# SX1278_STM32.net
KiCad netlist of a schematic drawn in Altium Designer
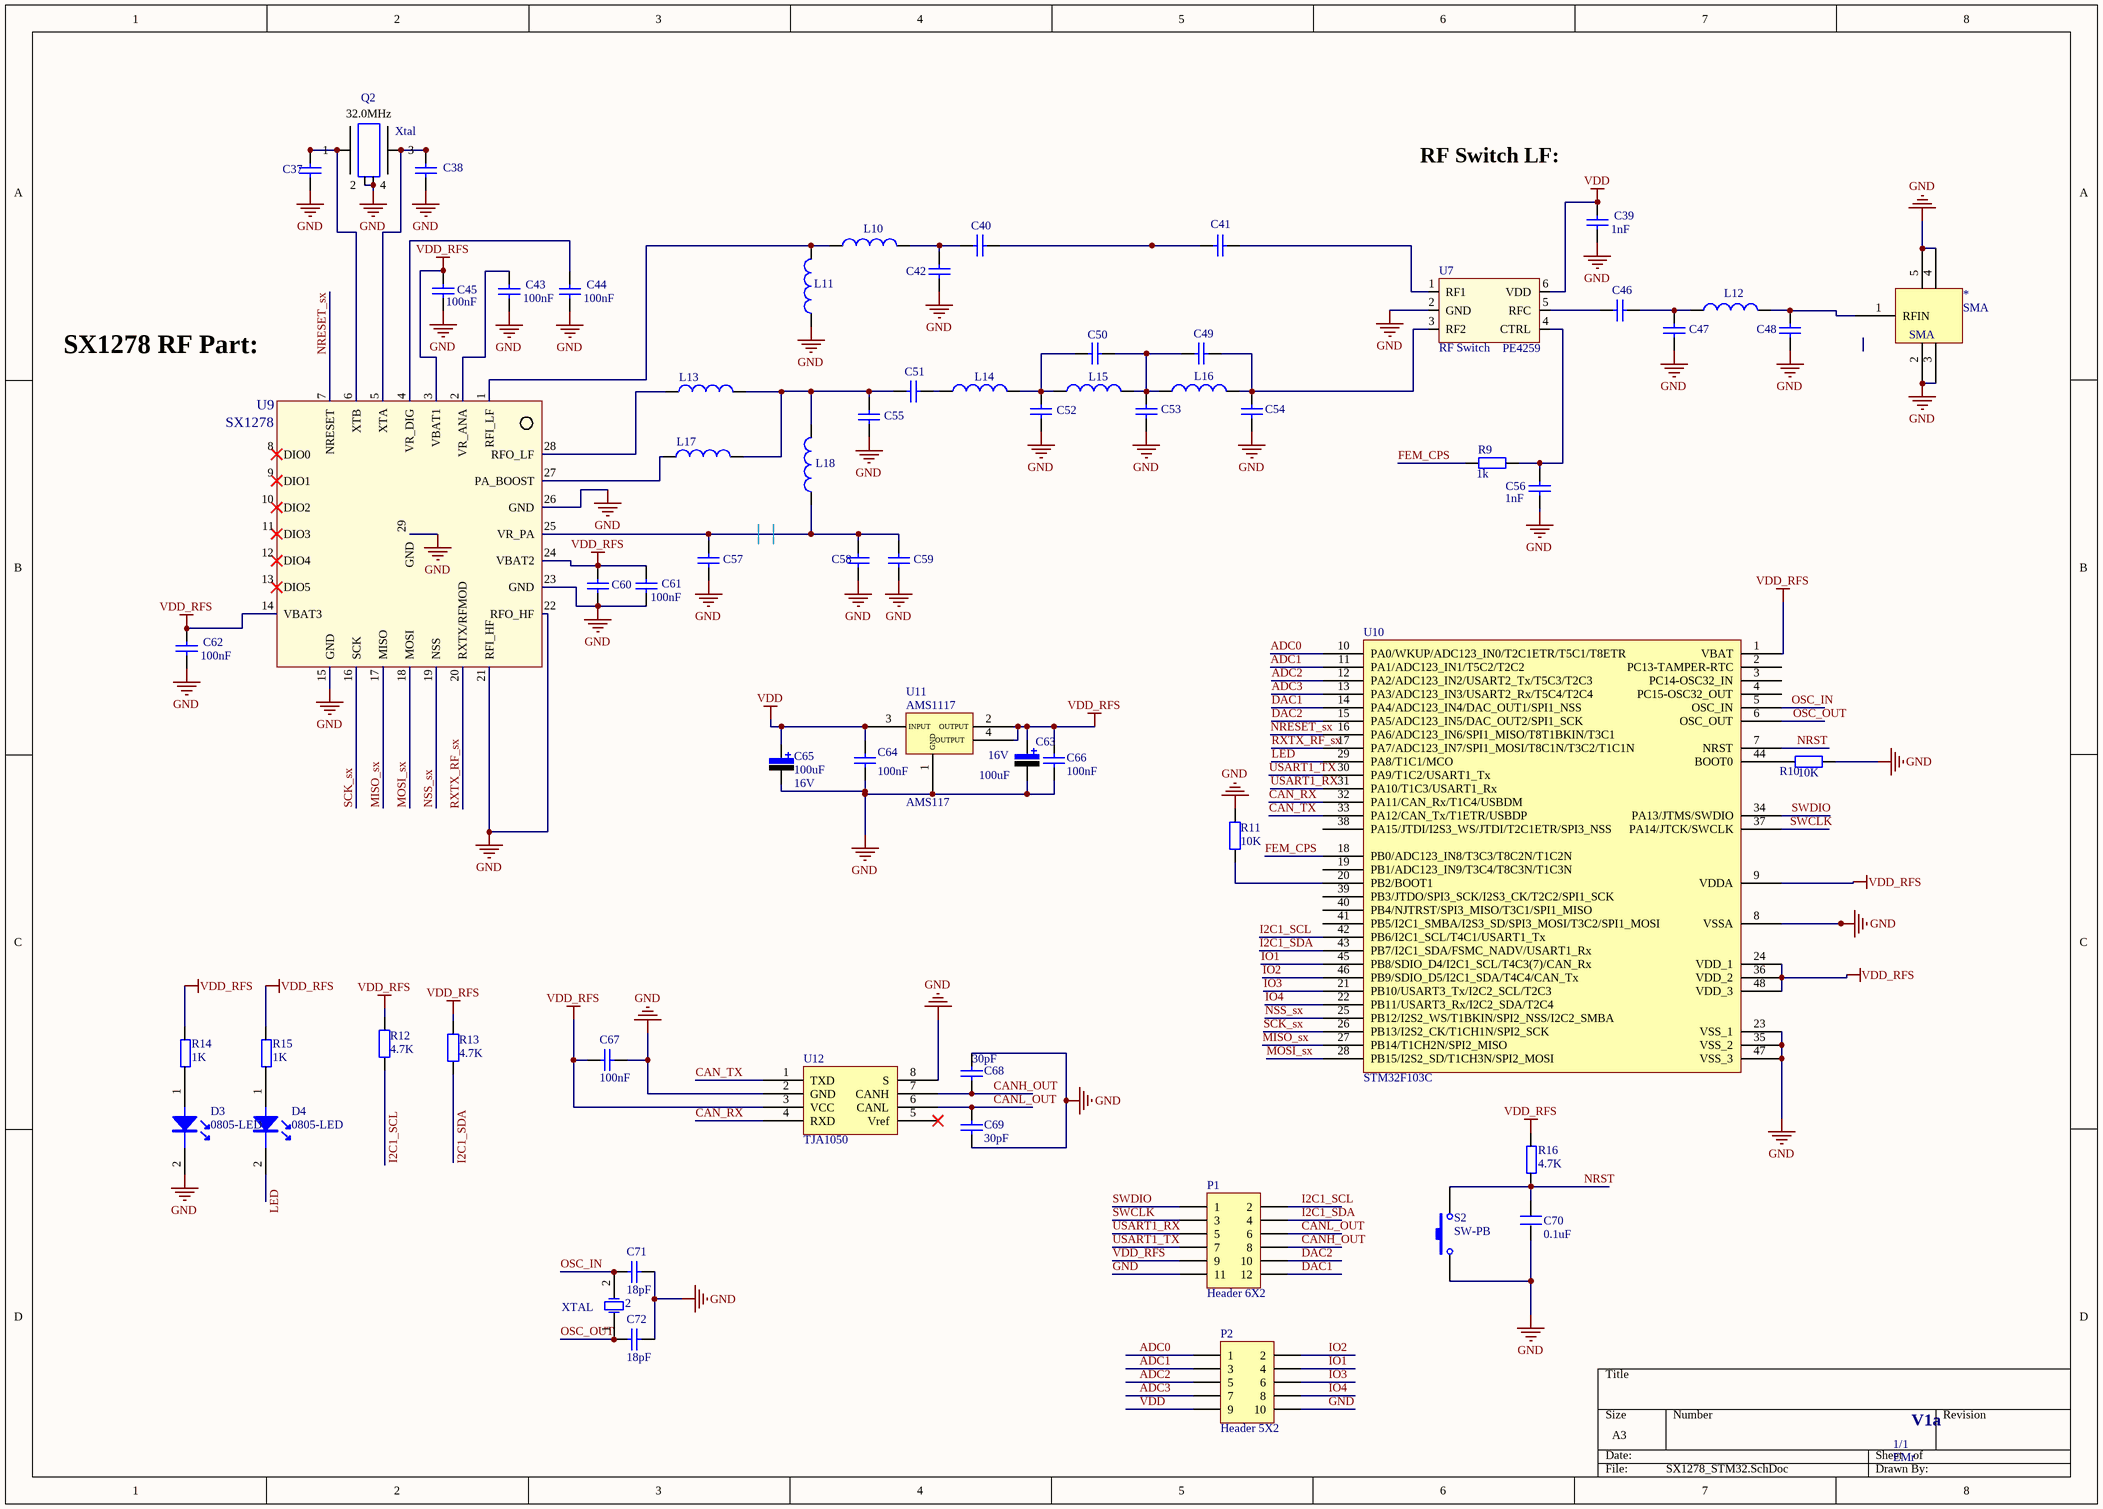
[diagram p0: SX1278_STM32.SchDoc]

(export (version "E")
  (design (tool "Eeschema 10.0.6"))
  (components
    (comp (ref "*") (value "SMA") (footprint "SMA") (libsource (lib "WFB_LIB") (part "SMA")))
    (comp (ref "2")
      (value "XTAL")
      (footprint "X-HC49U")
      (description "Crystal Oscillator")
      (fields (field (name "PUBLISHER") "Altium Limited"))
      (libsource (lib "Miscellaneous Devices") (part "XTAL"))
    )
    (comp (ref "C37")
      (value "Cap")
      (footprint "0603-2")
      (description "Capacitor SMD")
      (fields (field (name "PUBLISHER") "Altium Limited"))
      (libsource (lib "SX1276_e268v01a") (part "Cap"))
    )
    (comp (ref "C38")
      (value "Cap")
      (footprint "0603-2")
      (description "Capacitor SMD")
      (fields (field (name "PUBLISHER") "Altium Limited"))
      (libsource (lib "SX1276_e268v01a") (part "Cap"))
    )
    (comp (ref "C39")
      (value "1nF")
      (footprint "0603-2")
      (description "Capacitor SMD")
      (fields (field (name "Comment") "Cap") (field (name "PUBLISHER") "Altium Limited"))
      (libsource (lib "SX1276_e268v01a") (part "Cap"))
    )
    (comp (ref "C40")
      (value "Cap")
      (footprint "0603-2")
      (description "Capacitor SMD")
      (fields (field (name "PUBLISHER") "Altium Limited"))
      (libsource (lib "SX1276_e268v01a") (part "Cap"))
    )
    (comp (ref "C41")
      (value "Cap")
      (footprint "0603-2")
      (description "Capacitor SMD")
      (fields (field (name "PUBLISHER") "Altium Limited"))
      (libsource (lib "SX1276_e268v01a") (part "Cap"))
    )
    (comp (ref "C42")
      (value "Cap")
      (footprint "0603-2")
      (description "Capacitor SMD")
      (fields (field (name "PUBLISHER") "Altium Limited"))
      (libsource (lib "SX1276_e268v01a") (part "Cap"))
    )
    (comp (ref "C43")
      (value "100nF")
      (footprint "0603-2")
      (description "Capacitor SMD")
      (fields (field (name "Comment") "Cap") (field (name "PUBLISHER") "Altium Limited"))
      (libsource (lib "SX1276_e268v01a") (part "Cap"))
    )
    (comp (ref "C44")
      (value "100nF")
      (footprint "0603-2")
      (description "Capacitor SMD")
      (fields (field (name "Comment") "Cap") (field (name "PUBLISHER") "Altium Limited"))
      (libsource (lib "SX1276_e268v01a") (part "Cap"))
    )
    (comp (ref "C45")
      (value "100nF")
      (footprint "0603-2")
      (description "Capacitor SMD")
      (fields (field (name "Comment") "Cap") (field (name "PUBLISHER") "Altium Limited"))
      (libsource (lib "SX1276_e268v01a") (part "Cap"))
    )
    (comp (ref "C46")
      (value "Cap")
      (footprint "0603-2")
      (description "Capacitor SMD")
      (fields (field (name "PUBLISHER") "Altium Limited"))
      (libsource (lib "SX1276_e268v01a") (part "Cap"))
    )
    (comp (ref "C47")
      (value "Cap")
      (footprint "0603-2")
      (description "Capacitor SMD")
      (fields (field (name "PUBLISHER") "Altium Limited"))
      (libsource (lib "SX1276_e268v01a") (part "Cap"))
    )
    (comp (ref "C48")
      (value "Cap")
      (footprint "0603-2")
      (description "Capacitor SMD")
      (fields (field (name "PUBLISHER") "Altium Limited"))
      (libsource (lib "SX1276_e268v01a") (part "Cap"))
    )
    (comp (ref "C49")
      (value "Cap")
      (footprint "0603-2")
      (description "Capacitor SMD")
      (fields (field (name "PUBLISHER") "Altium Limited"))
      (libsource (lib "SX1276_e268v01a") (part "Cap"))
    )
    (comp (ref "C50")
      (value "Cap")
      (footprint "0603-2")
      (description "Capacitor SMD")
      (fields (field (name "PUBLISHER") "Altium Limited"))
      (libsource (lib "SX1276_e268v01a") (part "Cap"))
    )
    (comp (ref "C51")
      (value "Cap")
      (footprint "0603-2")
      (description "Capacitor SMD")
      (fields (field (name "PUBLISHER") "Altium Limited"))
      (libsource (lib "SX1276_e268v01a") (part "Cap"))
    )
    (comp (ref "C52")
      (value "Cap")
      (footprint "0603-2")
      (description "Capacitor SMD")
      (fields (field (name "PUBLISHER") "Altium Limited"))
      (libsource (lib "SX1276_e268v01a") (part "Cap"))
    )
    (comp (ref "C53")
      (value "Cap")
      (footprint "0603-2")
      (description "Capacitor SMD")
      (fields (field (name "PUBLISHER") "Altium Limited"))
      (libsource (lib "SX1276_e268v01a") (part "Cap"))
    )
    (comp (ref "C54")
      (value "Cap")
      (footprint "0603-2")
      (description "Capacitor SMD")
      (fields (field (name "PUBLISHER") "Altium Limited"))
      (libsource (lib "SX1276_e268v01a") (part "Cap"))
    )
    (comp (ref "C55")
      (value "Cap")
      (footprint "0603-2")
      (description "Capacitor SMD")
      (fields (field (name "PUBLISHER") "Altium Limited"))
      (libsource (lib "SX1276_e268v01a") (part "Cap"))
    )
    (comp (ref "C56")
      (value "1nF")
      (footprint "0603-2")
      (description "Capacitor SMD")
      (fields (field (name "Comment") "Cap") (field (name "PUBLISHER") "Altium Limited"))
      (libsource (lib "SX1276_e268v01a") (part "Cap"))
    )
    (comp (ref "C57")
      (value "Cap")
      (footprint "0603-2")
      (description "Capacitor SMD")
      (fields (field (name "PUBLISHER") "Altium Limited"))
      (libsource (lib "SX1276_e268v01a") (part "Cap"))
    )
    (comp (ref "C58")
      (value "Cap")
      (footprint "0603-2")
      (description "Capacitor SMD")
      (fields (field (name "PUBLISHER") "Altium Limited"))
      (libsource (lib "SX1276_e268v01a") (part "Cap"))
    )
    (comp (ref "C59")
      (value "Cap")
      (footprint "0603-2")
      (description "Capacitor SMD")
      (fields (field (name "PUBLISHER") "Altium Limited"))
      (libsource (lib "SX1276_e268v01a") (part "Cap"))
    )
    (comp (ref "C60")
      (value "Cap")
      (footprint "0603-2")
      (description "Capacitor SMD")
      (fields (field (name "PUBLISHER") "Altium Limited"))
      (libsource (lib "SX1276_e268v01a") (part "Cap"))
    )
    (comp (ref "C61")
      (value "100nF")
      (footprint "0603-2")
      (description "Capacitor SMD")
      (fields (field (name "Comment") "Cap") (field (name "PUBLISHER") "Altium Limited"))
      (libsource (lib "SX1276_e268v01a") (part "Cap"))
    )
    (comp (ref "C62")
      (value "100nF")
      (footprint "0603-2")
      (description "Capacitor SMD")
      (fields (field (name "Comment") "Cap") (field (name "PUBLISHER") "Altium Limited"))
      (libsource (lib "SX1276_e268v01a") (part "Cap"))
    )
    (comp (ref "C63")
      (value "100uF")
      (footprint "CAP-6032")
      (description "极性电解电容")
      (fields
        (field (name "VOL") "16V")
        (field (name "Comment") "Cap Pol")
        (field (name "PUBLISHER") "Altium Limited")
      )
      (libsource (lib "fszhang") (part "Cap Pol"))
    )
    (comp (ref "C64")
      (value "100nF")
      (footprint "0603-2")
      (description "无极性电容")
      (fields (field (name "Comment") "Cap") (field (name "PUBLISHER") "Altium Limited"))
      (libsource (lib "fszhang") (part "Cap"))
    )
    (comp (ref "C65")
      (value "100uF")
      (footprint "CAP-6032")
      (description "极性电解电容")
      (fields
        (field (name "VOL") "16V")
        (field (name "Comment") "Cap Pol")
        (field (name "PUBLISHER") "Altium Limited")
      )
      (libsource (lib "fszhang") (part "Cap Pol"))
    )
    (comp (ref "C66")
      (value "100nF")
      (footprint "0603-2")
      (description "无极性电容")
      (fields (field (name "Comment") "Cap") (field (name "PUBLISHER") "Altium Limited"))
      (libsource (lib "fszhang") (part "Cap"))
    )
    (comp (ref "C67")
      (value "100nF")
      (footprint "0603-2")
      (description "无极性电容")
      (fields (field (name "Comment") "Cap") (field (name "PUBLISHER") "Altium Limited"))
      (libsource (lib "fszhang") (part "Cap"))
    )
    (comp (ref "C68")
      (value "30pF")
      (footprint "0603-2")
      (description "无极性电容")
      (fields (field (name "Comment") "Cap") (field (name "PUBLISHER") "Altium Limited"))
      (libsource (lib "fszhang") (part "Cap"))
    )
    (comp (ref "C69")
      (value "30pF")
      (footprint "0603-2")
      (description "无极性电容")
      (fields (field (name "Comment") "Cap") (field (name "PUBLISHER") "Altium Limited"))
      (libsource (lib "fszhang") (part "Cap"))
    )
    (comp (ref "C70") (value "0.1uF") (footprint "0603-2") (libsource (lib "ATK-MPU6050六轴传感器模块") (part "C")))
    (comp (ref "C71")
      (value "18pF")
      (footprint "0603-2")
      (description "无极性电容")
      (fields (field (name "Comment") "Cap") (field (name "PUBLISHER") "Altium Limited"))
      (libsource (lib "fszhang") (part "Cap"))
    )
    (comp (ref "C72")
      (value "18pF")
      (footprint "0603-2")
      (description "无极性电容")
      (fields (field (name "Comment") "Cap") (field (name "PUBLISHER") "Altium Limited"))
      (libsource (lib "fszhang") (part "Cap"))
    )
    (comp (ref "D3")
      (value "0805-LED")
      (footprint "LED_0805")
      (libsource (lib "光敏电阻Guangmin") (part "0805-LED"))
    )
    (comp (ref "D4")
      (value "0805-LED")
      (footprint "LED_0805")
      (libsource (lib "光敏电阻Guangmin") (part "0805-LED"))
    )
    (comp (ref "L10")
      (value "Inductor")
      (footprint "0603-2")
      (description "Inductor SMD")
      (fields (field (name "PUBLISHER") "Altium Limited"))
      (libsource (lib "SX1276_e268v01a") (part "Inductor"))
    )
    (comp (ref "L11")
      (value "Inductor")
      (footprint "0603-2")
      (description "Inductor SMD")
      (fields (field (name "PUBLISHER") "Altium Limited"))
      (libsource (lib "SX1276_e268v01a") (part "Inductor"))
    )
    (comp (ref "L12")
      (value "Inductor")
      (footprint "0603-2")
      (description "Inductor SMD")
      (fields (field (name "PUBLISHER") "Altium Limited"))
      (libsource (lib "SX1276_e268v01a") (part "Inductor"))
    )
    (comp (ref "L13")
      (value "Inductor")
      (footprint "0603-2")
      (description "Inductor SMD")
      (fields (field (name "PUBLISHER") "Altium Limited"))
      (libsource (lib "SX1276_e268v01a") (part "Inductor"))
    )
    (comp (ref "L14")
      (value "Inductor")
      (footprint "0603-2")
      (description "Inductor SMD")
      (fields (field (name "PUBLISHER") "Altium Limited"))
      (libsource (lib "SX1276_e268v01a") (part "Inductor"))
    )
    (comp (ref "L15")
      (value "Inductor")
      (footprint "0603-2")
      (description "Inductor SMD")
      (fields (field (name "PUBLISHER") "Altium Limited"))
      (libsource (lib "SX1276_e268v01a") (part "Inductor"))
    )
    (comp (ref "L16")
      (value "Inductor")
      (footprint "0603-2")
      (description "Inductor SMD")
      (fields (field (name "PUBLISHER") "Altium Limited"))
      (libsource (lib "SX1276_e268v01a") (part "Inductor"))
    )
    (comp (ref "L17")
      (value "Inductor")
      (footprint "0603-2")
      (description "Inductor SMD")
      (fields (field (name "PUBLISHER") "Altium Limited"))
      (libsource (lib "SX1276_e268v01a") (part "Inductor"))
    )
    (comp (ref "L18")
      (value "Inductor")
      (footprint "0603-2")
      (description "Inductor SMD")
      (fields (field (name "PUBLISHER") "Altium Limited"))
      (libsource (lib "SX1276_e268v01a") (part "Inductor"))
    )
    (comp (ref "P1")
      (value "Header 6X2")
      (footprint "HDR2X6")
      (description "Header, 6-Pin, Dual row")
      (fields (field (name "PUBLISHER") "Altium Limited"))
      (libsource (lib "Miscellaneous Connectors") (part "Header 6X2"))
    )
    (comp (ref "P2")
      (value "Header 5X2")
      (footprint "HDR2X5")
      (description "Header, 5-Pin, Dual row")
      (fields (field (name "PUBLISHER") "Altium Limited"))
      (libsource (lib "Miscellaneous Connectors") (part "Header 5X2"))
    )
    (comp (ref "Q2")
      (value "Xtal")
      (footprint "X-CPX35")
      (description "Crystal with GND pins")
      (fields (field (name "ALTIUM_VALUE") "32.0MHz"))
      (libsource (lib "SX1276_e268v01a") (part "Xtal GND"))
    )
    (comp (ref "R9")
      (value "1k")
      (footprint "0603-2")
      (description "Resistor SMD - IEC symbol version")
      (fields (field (name "Comment") "Resistor"))
      (libsource (lib "SX1276_e268v01a") (part "Resistor"))
    )
    (comp (ref "R10")
      (value "10K")
      (footprint "0603-2")
      (description "贴片电阻")
      (fields (field (name "Comment") "Res1") (field (name "PUBLISHER") "Altium Limited"))
      (libsource (lib "") (part "Res1_1"))
    )
    (comp (ref "R11")
      (value "10K")
      (footprint "0603-2")
      (description "贴片电阻")
      (fields (field (name "Comment") "Res1") (field (name "PUBLISHER") "Altium Limited"))
      (libsource (lib "fszhang") (part "Res1"))
    )
    (comp (ref "R12")
      (value "4.7K")
      (footprint "0603-2")
      (description "贴片电阻")
      (fields (field (name "Comment") "Res1") (field (name "PUBLISHER") "Altium Limited"))
      (libsource (lib "fszhang") (part "Res1"))
    )
    (comp (ref "R13")
      (value "4.7K")
      (footprint "0603-2")
      (description "贴片电阻")
      (fields (field (name "Comment") "Res1") (field (name "PUBLISHER") "Altium Limited"))
      (libsource (lib "fszhang") (part "Res1"))
    )
    (comp (ref "R14") (value "1K") (footprint "0603-2") (libsource (lib "ATK-MPU6050六轴传感器模块") (part "R")))
    (comp (ref "R15") (value "1K") (footprint "0603-2") (libsource (lib "ATK-MPU6050六轴传感器模块") (part "R")))
    (comp (ref "R16") (value "4.7K") (footprint "0603-2") (libsource (lib "ATK-MPU6050六轴传感器模块") (part "R")))
    (comp (ref "S2")
      (value "SW-PB")
      (footprint "SW_PB2_A1")
      (description "微动开关")
      (fields (field (name "PUBLISHER") "Altium Limited"))
      (libsource (lib "fszhang") (part "SW-PB"))
    )
    (comp (ref "U7")
      (value "RF Switch")
      (footprint "SC70-6")
      (description "PE4259 Peregrine RF Switch")
      (fields (field (name "ALTIUM_VALUE") "PE4259"))
      (libsource (lib "SX1276_e268v01a") (part "PE4259 RF Switch"))
    )
    (comp (ref "U9")
      (value "SX1278")
      (footprint "vqfn28_6x6mm")
      (description "SX1276 - Low Power Integrated UHF Transceiver with loRa Modem")
      (libsource (lib "SX1276_e268v01a") (part "SX1276"))
    )
    (comp (ref "U10")
      (value "STM32F103C")
      (footprint "STM32F103C8T6")
      (description "STM32单片机48引脚")
      (libsource (lib "fszhang") (part "STM32F103C"))
    )
    (comp (ref "U11") (value "AMS117") (footprint "AMS1117") (libsource (lib "STM32") (part "AMS117")))
    (comp (ref "U12") (value "TJA1050") (footprint "VP230") (libsource (lib "STM32") (part "TJA1050")))
  )
  (nets
    (net (code "1") (name "/ADC0") (class "Default")
      (node (ref "P2") (pin "1") (pinfunction "1_1") (pintype "passive"))
      (node (ref "U10") (pin "10") (pinfunction "PA0/WKUP/ADC123_IN0/T2C1ETR/T5C1/T8ETR_10") (pintype "passive"))
    )
    (net (code "2") (name "/ADC1") (class "Default")
      (node (ref "P2") (pin "3") (pinfunction "3_3") (pintype "passive"))
      (node (ref "U10") (pin "11") (pinfunction "PA1/ADC123_IN1/T5C2/T2C2_11") (pintype "passive"))
    )
    (net (code "3") (name "/ADC2") (class "Default")
      (node (ref "P2") (pin "5") (pinfunction "5_5") (pintype "passive"))
      (node (ref "U10") (pin "12") (pinfunction "PA2/ADC123_IN2/USART2_Tx/T5C3/T2C3_12") (pintype "passive"))
    )
    (net (code "4") (name "/ADC3") (class "Default")
      (node (ref "P2") (pin "7") (pinfunction "7_7") (pintype "passive"))
      (node (ref "U10") (pin "13") (pinfunction "PA3/ADC123_IN3/USART2_Rx/T5C4/T2C4_13") (pintype "passive"))
    )
    (net (code "5") (name "/CANH_OUT") (class "Default")
      (node (ref "C68") (pin "1") (pinfunction "1_1") (pintype "passive"))
      (node (ref "P1") (pin "8") (pinfunction "8_8") (pintype "passive"))
      (node (ref "U12") (pin "7") (pinfunction "CANH_7") (pintype "passive"))
    )
    (net (code "6") (name "/CANL_OUT") (class "Default")
      (node (ref "C69") (pin "2") (pinfunction "2_2") (pintype "passive"))
      (node (ref "P1") (pin "6") (pinfunction "6_6") (pintype "passive"))
      (node (ref "U12") (pin "6") (pinfunction "CANL_6") (pintype "passive"))
    )
    (net (code "7") (name "/CAN_RX") (class "Default")
      (node (ref "U10") (pin "32") (pinfunction "PA11/CAN_Rx/T1C4/USBDM_32") (pintype "passive"))
      (node (ref "U12") (pin "4") (pinfunction "RXD_4") (pintype "passive"))
    )
    (net (code "8") (name "/CAN_TX") (class "Default")
      (node (ref "U10") (pin "33") (pinfunction "PA12/CAN_Tx/T1ETR/USBDP_33") (pintype "passive"))
      (node (ref "U12") (pin "1") (pinfunction "TXD_1") (pintype "passive"))
    )
    (net (code "9") (name "/DAC1") (class "Default")
      (node (ref "P1") (pin "12") (pinfunction "12_12") (pintype "passive"))
      (node (ref "U10") (pin "14") (pinfunction "PA4/ADC123_IN4/DAC_OUT1/SPI1_NSS_14") (pintype "passive"))
    )
    (net (code "10") (name "/DAC2") (class "Default")
      (node (ref "P1") (pin "10") (pinfunction "10_10") (pintype "passive"))
      (node (ref "U10") (pin "15") (pinfunction "PA5/ADC123_IN5/DAC_OUT2/SPI1_SCK_15") (pintype "passive"))
    )
    (net (code "11") (name "/FEM_CPS") (class "Default")
      (node (ref "R9") (pin "2") (pinfunction "2_2") (pintype "passive"))
      (node (ref "U10") (pin "18") (pinfunction "PB0/ADC123_IN8/T3C3/T8C2N/T1C2N_18") (pintype "passive"))
    )
    (net (code "12") (name "/I2C1_SCL") (class "Default")
      (node (ref "P1") (pin "2") (pinfunction "2_2") (pintype "passive"))
      (node (ref "R12") (pin "1") (pinfunction "1_1") (pintype "passive"))
      (node (ref "U10") (pin "42") (pinfunction "PB6/I2C1_SCL/T4C1/USART1_Tx_42") (pintype "passive"))
    )
    (net (code "13") (name "/I2C1_SDA") (class "Default")
      (node (ref "P1") (pin "4") (pinfunction "4_4") (pintype "passive"))
      (node (ref "R13") (pin "1") (pinfunction "1_1") (pintype "passive"))
      (node (ref "U10") (pin "43") (pinfunction "PB7/I2C1_SDA/FSMC_NADV/USART1_Rx_43") (pintype "passive"))
    )
    (net (code "14") (name "/IO1") (class "Default")
      (node (ref "P2") (pin "4") (pinfunction "4_4") (pintype "passive"))
      (node (ref "U10") (pin "45") (pinfunction "PB8/SDIO_D4/I2C1_SCL/T4C3(7)/CAN_Rx_45") (pintype "passive"))
    )
    (net (code "15") (name "/IO2") (class "Default")
      (node (ref "P2") (pin "2") (pinfunction "2_2") (pintype "passive"))
      (node (ref "U10") (pin "46") (pinfunction "PB9/SDIO_D5/I2C1_SDA/T4C4/CAN_Tx_46") (pintype "passive"))
    )
    (net (code "16") (name "/IO3") (class "Default")
      (node (ref "P2") (pin "6") (pinfunction "6_6") (pintype "passive"))
      (node (ref "U10") (pin "21") (pinfunction "PB10/USART3_Tx/I2C2_SCL/T2C3_21") (pintype "passive"))
    )
    (net (code "17") (name "/IO4") (class "Default")
      (node (ref "P2") (pin "8") (pinfunction "8_8") (pintype "passive"))
      (node (ref "U10") (pin "22") (pinfunction "PB11/USART3_Rx/I2C2_SDA/T2C4_22") (pintype "passive"))
    )
    (net (code "18") (name "/LED") (class "Default")
      (node (ref "D4") (pin "2") (pinfunction "2_2") (pintype "passive"))
      (node (ref "U10") (pin "29") (pinfunction "PA8/T1C1/MCO_29") (pintype "passive"))
    )
    (net (code "19") (name "/MISO_sx") (class "Default")
      (node (ref "U10") (pin "27") (pinfunction "PB14/T1CH2N/SPI2_MISO_27") (pintype "passive"))
      (node (ref "U9") (pin "17") (pinfunction "MISO_17") (pintype "passive"))
    )
    (net (code "20") (name "/MOSI_sx") (class "Default")
      (node (ref "U10") (pin "28") (pinfunction "PB15/I2S2_SD/T1CH3N/SPI2_MOSI_28") (pintype "passive"))
      (node (ref "U9") (pin "18") (pinfunction "MOSI_18") (pintype "passive"))
    )
    (net (code "21") (name "/NRESET_sx") (class "Default")
      (node (ref "U10") (pin "16") (pinfunction "PA6/ADC123_IN6/SPI1_MISO/T8T1BKIN/T3C1_16") (pintype "passive"))
      (node (ref "U9") (pin "7") (pinfunction "NRESET_7") (pintype "passive"))
    )
    (net (code "22") (name "/NRST") (class "Default")
      (node (ref "C70") (pin "2") (pintype "passive"))
      (node (ref "R16") (pin "1") (pintype "passive"))
      (node (ref "S2") (pin "2") (pinfunction "2_2") (pintype "passive"))
      (node (ref "U10") (pin "7") (pinfunction "NRST_7") (pintype "passive"))
    )
    (net (code "23") (name "/NSS_sx") (class "Default")
      (node (ref "U10") (pin "25") (pinfunction "PB12/I2S2_WS/T1BKIN/SPI2_NSS/I2C2_SMBA_25") (pintype "passive"))
      (node (ref "U9") (pin "19") (pinfunction "NSS_19") (pintype "passive"))
    )
    (net (code "24") (name "/OSC_IN") (class "Default")
      (node (ref "2") (pin "2") (pinfunction "OSC2_2") (pintype "passive"))
      (node (ref "C71") (pin "1") (pinfunction "1_1") (pintype "passive"))
      (node (ref "U10") (pin "5") (pinfunction "OSC_IN_5") (pintype "passive"))
    )
    (net (code "25") (name "/OSC_OUT") (class "Default")
      (node (ref "2") (pin "1") (pinfunction "OSC1_1") (pintype "passive"))
      (node (ref "C72") (pin "1") (pinfunction "1_1") (pintype "passive"))
      (node (ref "U10") (pin "6") (pinfunction "OSC_OUT_6") (pintype "passive"))
    )
    (net (code "26") (name "/RXTX_RF_sx") (class "Default")
      (node (ref "U10") (pin "17") (pinfunction "PA7/ADC123_IN7/SPI1_MOSI/T8C1N/T3C2/T1C1N_17") (pintype "passive"))
      (node (ref "U9") (pin "20") (pinfunction "RXTX/RFMOD_20") (pintype "passive"))
    )
    (net (code "27") (name "/SCK_sx") (class "Default")
      (node (ref "U10") (pin "26") (pinfunction "PB13/I2S2_CK/T1CH1N/SPI2_SCK_26") (pintype "passive"))
      (node (ref "U9") (pin "16") (pinfunction "SCK_16") (pintype "passive"))
    )
    (net (code "28") (name "/SWCLK") (class "Default")
      (node (ref "P1") (pin "3") (pinfunction "3_3") (pintype "passive"))
      (node (ref "U10") (pin "37") (pinfunction "PA14/JTCK/SWCLK_37") (pintype "passive"))
    )
    (net (code "29") (name "/SWDIO") (class "Default")
      (node (ref "P1") (pin "1") (pinfunction "1_1") (pintype "passive"))
      (node (ref "U10") (pin "34") (pinfunction "PA13/JTMS/SWDIO_34") (pintype "passive"))
    )
    (net (code "30") (name "/USART1_RX") (class "Default")
      (node (ref "P1") (pin "5") (pinfunction "5_5") (pintype "passive"))
      (node (ref "U10") (pin "31") (pinfunction "PA10/T1C3/USART1_Rx_31") (pintype "passive"))
    )
    (net (code "31") (name "/USART1_TX") (class "Default")
      (node (ref "P1") (pin "7") (pinfunction "7_7") (pintype "passive"))
      (node (ref "U10") (pin "30") (pinfunction "PA9/T1C2/USART1_Tx_30") (pintype "passive"))
    )
    (net (code "32") (name "GND") (class "Default")
      (node (ref "*") (pin "2") (pintype "passive"))
      (node (ref "*") (pin "3") (pintype "passive"))
      (node (ref "*") (pin "4") (pintype "passive"))
      (node (ref "*") (pin "5") (pintype "passive"))
      (node (ref "C37") (pin "1") (pinfunction "1_1") (pintype "passive"))
      (node (ref "C38") (pin "1") (pinfunction "1_1") (pintype "passive"))
      (node (ref "C39") (pin "1") (pinfunction "1_1") (pintype "passive"))
      (node (ref "C42") (pin "1") (pinfunction "1_1") (pintype "passive"))
      (node (ref "C43") (pin "1") (pinfunction "1_1") (pintype "passive"))
      (node (ref "C44") (pin "1") (pinfunction "1_1") (pintype "passive"))
      (node (ref "C45") (pin "1") (pinfunction "1_1") (pintype "passive"))
      (node (ref "C47") (pin "1") (pinfunction "1_1") (pintype "passive"))
      (node (ref "C48") (pin "1") (pinfunction "1_1") (pintype "passive"))
      (node (ref "C52") (pin "1") (pinfunction "1_1") (pintype "passive"))
      (node (ref "C53") (pin "1") (pinfunction "1_1") (pintype "passive"))
      (node (ref "C54") (pin "1") (pinfunction "1_1") (pintype "passive"))
      (node (ref "C55") (pin "1") (pinfunction "1_1") (pintype "passive"))
      (node (ref "C56") (pin "2") (pinfunction "2_2") (pintype "passive"))
      (node (ref "C57") (pin "1") (pinfunction "1_1") (pintype "passive"))
      (node (ref "C58") (pin "1") (pinfunction "1_1") (pintype "passive"))
      (node (ref "C59") (pin "1") (pinfunction "1_1") (pintype "passive"))
      (node (ref "C60") (pin "1") (pinfunction "1_1") (pintype "passive"))
      (node (ref "C61") (pin "1") (pinfunction "1_1") (pintype "passive"))
      (node (ref "C62") (pin "1") (pinfunction "1_1") (pintype "passive"))
      (node (ref "C63") (pin "2") (pinfunction "2_2") (pintype "passive"))
      (node (ref "C64") (pin "1") (pinfunction "1_1") (pintype "passive"))
      (node (ref "C65") (pin "2") (pinfunction "2_2") (pintype "passive"))
      (node (ref "C66") (pin "1") (pinfunction "1_1") (pintype "passive"))
      (node (ref "C67") (pin "2") (pinfunction "2_2") (pintype "passive"))
      (node (ref "C68") (pin "2") (pinfunction "2_2") (pintype "passive"))
      (node (ref "C69") (pin "1") (pinfunction "1_1") (pintype "passive"))
      (node (ref "C70") (pin "1") (pintype "passive"))
      (node (ref "C71") (pin "2") (pinfunction "2_2") (pintype "passive"))
      (node (ref "C72") (pin "2") (pinfunction "2_2") (pintype "passive"))
      (node (ref "D3") (pin "2") (pinfunction "2_2") (pintype "passive"))
      (node (ref "L11") (pin "1") (pinfunction "1_1") (pintype "passive"))
      (node (ref "P1") (pin "11") (pinfunction "11_11") (pintype "passive"))
      (node (ref "P2") (pin "10") (pinfunction "10_10") (pintype "passive"))
      (node (ref "Q2") (pin "2") (pinfunction "2_2") (pintype "passive"))
      (node (ref "Q2") (pin "4") (pinfunction "4_4") (pintype "passive"))
      (node (ref "R10") (pin "2") (pinfunction "2_2") (pintype "passive"))
      (node (ref "R11") (pin "2") (pinfunction "2_2") (pintype "passive"))
      (node (ref "S2") (pin "1") (pinfunction "1_1") (pintype "passive"))
      (node (ref "U10") (pin "23") (pinfunction "VSS_1_23") (pintype "passive"))
      (node (ref "U10") (pin "35") (pinfunction "VSS_2_35") (pintype "passive"))
      (node (ref "U10") (pin "47") (pinfunction "VSS_3_47") (pintype "passive"))
      (node (ref "U10") (pin "8") (pinfunction "VSSA_8") (pintype "passive"))
      (node (ref "U11") (pin "1") (pinfunction "GND_1") (pintype "passive"))
      (node (ref "U12") (pin "2") (pinfunction "GND_2") (pintype "passive"))
      (node (ref "U12") (pin "8") (pinfunction "S_8") (pintype "passive"))
      (node (ref "U7") (pin "2") (pinfunction "GND_2") (pintype "passive"))
      (node (ref "U9") (pin "15") (pinfunction "GND_15") (pintype "passive"))
      (node (ref "U9") (pin "21") (pinfunction "RFI_HF_21") (pintype "passive"))
      (node (ref "U9") (pin "22") (pinfunction "RFO_HF_22") (pintype "passive"))
      (node (ref "U9") (pin "23") (pinfunction "GND_23") (pintype "passive"))
      (node (ref "U9") (pin "26") (pinfunction "GND_26") (pintype "passive"))
      (node (ref "U9") (pin "29") (pinfunction "GND_29") (pintype "passive"))
    )
    (net (code "33") (name "Net-(*-RFIN)") (class "Default")
      (node (ref "*") (pin "1") (pinfunction "RFIN_1") (pintype "passive"))
      (node (ref "C48") (pin "2") (pinfunction "2_2") (pintype "passive"))
      (node (ref "L12") (pin "2") (pinfunction "2_2") (pintype "passive"))
    )
    (net (code "34") (name "Net-(C40-Pad1)") (class "Default")
      (node (ref "C40") (pin "1") (pinfunction "1_1") (pintype "passive"))
      (node (ref "C41") (pin "2") (pinfunction "2_2") (pintype "passive"))
    )
    (net (code "35") (name "Net-(C40-Pad2)") (class "Default")
      (node (ref "C40") (pin "2") (pinfunction "2_2") (pintype "passive"))
      (node (ref "C42") (pin "2") (pinfunction "2_2") (pintype "passive"))
      (node (ref "L10") (pin "2") (pinfunction "2_2") (pintype "passive"))
    )
    (net (code "36") (name "Net-(C46-Pad1)") (class "Default")
      (node (ref "C46") (pin "1") (pinfunction "1_1") (pintype "passive"))
      (node (ref "C47") (pin "2") (pinfunction "2_2") (pintype "passive"))
      (node (ref "L12") (pin "1") (pinfunction "1_1") (pintype "passive"))
    )
    (net (code "37") (name "Net-(C49-Pad2)") (class "Default")
      (node (ref "C49") (pin "2") (pinfunction "2_2") (pintype "passive"))
      (node (ref "C50") (pin "1") (pinfunction "1_1") (pintype "passive"))
      (node (ref "C53") (pin "2") (pinfunction "2_2") (pintype "passive"))
      (node (ref "L15") (pin "2") (pinfunction "2_2") (pintype "passive"))
      (node (ref "L16") (pin "1") (pinfunction "1_1") (pintype "passive"))
    )
    (net (code "38") (name "Net-(C50-Pad2)") (class "Default")
      (node (ref "C50") (pin "2") (pinfunction "2_2") (pintype "passive"))
      (node (ref "C52") (pin "2") (pinfunction "2_2") (pintype "passive"))
      (node (ref "L14") (pin "2") (pinfunction "2_2") (pintype "passive"))
      (node (ref "L15") (pin "1") (pinfunction "1_1") (pintype "passive"))
    )
    (net (code "39") (name "Net-(C51-Pad1)") (class "Default")
      (node (ref "C51") (pin "1") (pinfunction "1_1") (pintype "passive"))
      (node (ref "L14") (pin "1") (pinfunction "1_1") (pintype "passive"))
    )
    (net (code "40") (name "Net-(C51-Pad2)") (class "Default")
      (node (ref "C51") (pin "2") (pinfunction "2_2") (pintype "passive"))
      (node (ref "C55") (pin "2") (pinfunction "2_2") (pintype "passive"))
      (node (ref "L13") (pin "2") (pinfunction "2_2") (pintype "passive"))
      (node (ref "L17") (pin "2") (pinfunction "2_2") (pintype "passive"))
      (node (ref "L18") (pin "2") (pinfunction "2_2") (pintype "passive"))
    )
    (net (code "41") (name "Net-(D3-Pad1)") (class "Default")
      (node (ref "D3") (pin "1") (pinfunction "1_1") (pintype "passive"))
      (node (ref "R14") (pin "1") (pintype "passive"))
    )
    (net (code "42") (name "Net-(D4-Pad1)") (class "Default")
      (node (ref "D4") (pin "1") (pinfunction "1_1") (pintype "passive"))
      (node (ref "R15") (pin "1") (pintype "passive"))
    )
    (net (code "43") (name "Net-(U7-CTRL)") (class "Default")
      (node (ref "C56") (pin "1") (pinfunction "1_1") (pintype "passive"))
      (node (ref "R9") (pin "1") (pinfunction "1_1") (pintype "passive"))
      (node (ref "U7") (pin "4") (pinfunction "CTRL_4") (pintype "passive"))
    )
    (net (code "44") (name "Net-(U7-RF1)") (class "Default")
      (node (ref "C41") (pin "1") (pinfunction "1_1") (pintype "passive"))
      (node (ref "U7") (pin "1") (pinfunction "RF1_1") (pintype "passive"))
    )
    (net (code "45") (name "Net-(U7-RF2)") (class "Default")
      (node (ref "C49") (pin "1") (pinfunction "1_1") (pintype "passive"))
      (node (ref "C54") (pin "2") (pinfunction "2_2") (pintype "passive"))
      (node (ref "L16") (pin "2") (pinfunction "2_2") (pintype "passive"))
      (node (ref "U7") (pin "3") (pinfunction "RF2_3") (pintype "passive"))
    )
    (net (code "46") (name "Net-(U7-RFC)") (class "Default")
      (node (ref "C46") (pin "2") (pinfunction "2_2") (pintype "passive"))
      (node (ref "U7") (pin "5") (pinfunction "RFC_5") (pintype "passive"))
    )
    (net (code "47") (name "Net-(U9-PA_BOOST)") (class "Default")
      (node (ref "L17") (pin "1") (pinfunction "1_1") (pintype "passive"))
      (node (ref "U9") (pin "27") (pinfunction "PA_BOOST_27") (pintype "passive"))
    )
    (net (code "48") (name "Net-(U9-RFI_LF)") (class "Default")
      (node (ref "L10") (pin "1") (pinfunction "1_1") (pintype "passive"))
      (node (ref "L11") (pin "2") (pinfunction "2_2") (pintype "passive"))
      (node (ref "U9") (pin "1") (pinfunction "RFI_LF_1") (pintype "passive"))
    )
    (net (code "49") (name "Net-(U9-RFO_LF)") (class "Default")
      (node (ref "L13") (pin "1") (pinfunction "1_1") (pintype "passive"))
      (node (ref "U9") (pin "28") (pinfunction "RFO_LF_28") (pintype "passive"))
    )
    (net (code "50") (name "Net-(U9-VR_ANA)") (class "Default")
      (node (ref "C43") (pin "2") (pinfunction "2_2") (pintype "passive"))
      (node (ref "U9") (pin "2") (pinfunction "VR_ANA_2") (pintype "passive"))
    )
    (net (code "51") (name "Net-(U9-VR_DIG)") (class "Default")
      (node (ref "C44") (pin "2") (pinfunction "2_2") (pintype "passive"))
      (node (ref "U9") (pin "4") (pinfunction "VR_DIG_4") (pintype "passive"))
    )
    (net (code "52") (name "Net-(U9-VR_PA)") (class "Default")
      (node (ref "C57") (pin "2") (pinfunction "2_2") (pintype "passive"))
      (node (ref "C58") (pin "2") (pinfunction "2_2") (pintype "passive"))
      (node (ref "C59") (pin "2") (pinfunction "2_2") (pintype "passive"))
      (node (ref "L18") (pin "1") (pinfunction "1_1") (pintype "passive"))
      (node (ref "U9") (pin "25") (pinfunction "VR_PA_25") (pintype "passive"))
    )
    (net (code "53") (name "Net-(U9-XTA)") (class "Default")
      (node (ref "C38") (pin "2") (pinfunction "2_2") (pintype "passive"))
      (node (ref "Q2") (pin "3") (pinfunction "3_3") (pintype "passive"))
      (node (ref "U9") (pin "5") (pinfunction "XTA_5") (pintype "passive"))
    )
    (net (code "54") (name "Net-(U9-XTB)") (class "Default")
      (node (ref "C37") (pin "2") (pinfunction "2_2") (pintype "passive"))
      (node (ref "Q2") (pin "1") (pinfunction "1_1") (pintype "passive"))
      (node (ref "U9") (pin "6") (pinfunction "XTB_6") (pintype "passive"))
    )
    (net (code "55") (name "Net-(U10-BOOT0)") (class "Default")
      (node (ref "R10") (pin "1") (pinfunction "1_1") (pintype "passive"))
      (node (ref "U10") (pin "44") (pinfunction "BOOT0_44") (pintype "passive"))
    )
    (net (code "56") (name "Net-(U10-PB2{slash}BOOT1)") (class "Default")
      (node (ref "R11") (pin "1") (pinfunction "1_1") (pintype "passive"))
      (node (ref "U10") (pin "20") (pinfunction "PB2/BOOT1_20") (pintype "passive"))
    )
    (net (code "57") (name "VDD") (class "Default")
      (node (ref "C39") (pin "2") (pinfunction "2_2") (pintype "passive"))
      (node (ref "C64") (pin "2") (pinfunction "2_2") (pintype "passive"))
      (node (ref "C65") (pin "1") (pinfunction "1_1") (pintype "passive"))
      (node (ref "P2") (pin "9") (pinfunction "9_9") (pintype "passive"))
      (node (ref "U11") (pin "3") (pinfunction "INPUT_3") (pintype "passive"))
      (node (ref "U7") (pin "6") (pinfunction "VDD_6") (pintype "passive"))
    )
    (net (code "58") (name "VDD_RFS") (class "Default")
      (node (ref "C45") (pin "2") (pinfunction "2_2") (pintype "passive"))
      (node (ref "C60") (pin "2") (pinfunction "2_2") (pintype "passive"))
      (node (ref "C61") (pin "2") (pinfunction "2_2") (pintype "passive"))
      (node (ref "C62") (pin "2") (pinfunction "2_2") (pintype "passive"))
      (node (ref "C63") (pin "1") (pinfunction "1_1") (pintype "passive"))
      (node (ref "C66") (pin "2") (pinfunction "2_2") (pintype "passive"))
      (node (ref "C67") (pin "1") (pinfunction "1_1") (pintype "passive"))
      (node (ref "P1") (pin "9") (pinfunction "9_9") (pintype "passive"))
      (node (ref "R12") (pin "2") (pinfunction "2_2") (pintype "passive"))
      (node (ref "R13") (pin "2") (pinfunction "2_2") (pintype "passive"))
      (node (ref "R14") (pin "2") (pintype "passive"))
      (node (ref "R15") (pin "2") (pintype "passive"))
      (node (ref "R16") (pin "2") (pintype "passive"))
      (node (ref "U10") (pin "1") (pinfunction "VBAT_1") (pintype "passive"))
      (node (ref "U10") (pin "24") (pinfunction "VDD_1_24") (pintype "passive"))
      (node (ref "U10") (pin "36") (pinfunction "VDD_2_36") (pintype "passive"))
      (node (ref "U10") (pin "48") (pinfunction "VDD_3_48") (pintype "passive"))
      (node (ref "U10") (pin "9") (pinfunction "VDDA_9") (pintype "passive"))
      (node (ref "U11") (pin "2") (pinfunction "OUTPUT_2") (pintype "passive"))
      (node (ref "U11") (pin "4") (pinfunction "OUTPUT_4") (pintype "passive"))
      (node (ref "U12") (pin "3") (pinfunction "VCC_3") (pintype "passive"))
      (node (ref "U9") (pin "14") (pinfunction "VBAT3_14") (pintype "passive"))
      (node (ref "U9") (pin "24") (pinfunction "VBAT2_24") (pintype "passive"))
      (node (ref "U9") (pin "3") (pinfunction "VBAT1_3") (pintype "passive"))
    )
    (net (code "59") (name "unconnected-(U9-DIO0-Pad8)") (class "Default")
      (node (ref "U9") (pin "8") (pinfunction "DIO0_8") (pintype "passive+no_connect"))
    )
    (net (code "60") (name "unconnected-(U9-DIO1-Pad9)") (class "Default")
      (node (ref "U9") (pin "9") (pinfunction "DIO1_9") (pintype "passive+no_connect"))
    )
    (net (code "61") (name "unconnected-(U9-DIO2-Pad10)") (class "Default")
      (node (ref "U9") (pin "10") (pinfunction "DIO2_10") (pintype "passive+no_connect"))
    )
    (net (code "62") (name "unconnected-(U9-DIO3-Pad11)") (class "Default")
      (node (ref "U9") (pin "11") (pinfunction "DIO3_11") (pintype "passive+no_connect"))
    )
    (net (code "63") (name "unconnected-(U9-DIO4-Pad12)") (class "Default")
      (node (ref "U9") (pin "12") (pinfunction "DIO4_12") (pintype "passive+no_connect"))
    )
    (net (code "64") (name "unconnected-(U9-DIO5-Pad13)") (class "Default")
      (node (ref "U9") (pin "13") (pinfunction "DIO5_13") (pintype "passive+no_connect"))
    )
    (net (code "65") (name "unconnected-(U10-PA15{slash}JTDI{slash}I2S3_WS{slash}JTDI{slash}T2C1ETR{slash}SPI3_NSS-Pad38)") (class "Default")
      (node (ref "U10") (pin "38") (pinfunction "PA15/JTDI/I2S3_WS/JTDI/T2C1ETR/SPI3_NSS_38") (pintype "passive"))
    )
    (net (code "66") (name "unconnected-(U10-PB1{slash}ADC123_IN9{slash}T3C4{slash}T8C3N{slash}T1C3N-Pad19)") (class "Default")
      (node (ref "U10") (pin "19") (pinfunction "PB1/ADC123_IN9/T3C4/T8C3N/T1C3N_19") (pintype "passive"))
    )
    (net (code "67") (name "unconnected-(U10-PB3{slash}JTDO{slash}SPI3_SCK{slash}I2S3_CK{slash}T2C2{slash}SPI1_SCK-Pad39)") (class "Default")
      (node (ref "U10") (pin "39") (pinfunction "PB3/JTDO/SPI3_SCK/I2S3_CK/T2C2/SPI1_SCK_39") (pintype "passive"))
    )
    (net (code "68") (name "unconnected-(U10-PB4{slash}NJTRST{slash}SPI3_MISO{slash}T3C1{slash}SPI1_MISO-Pad40)") (class "Default")
      (node (ref "U10") (pin "40") (pinfunction "PB4/NJTRST/SPI3_MISO/T3C1/SPI1_MISO_40") (pintype "passive"))
    )
    (net (code "69") (name "unconnected-(U10-PB5{slash}I2C1_SMBA{slash}I2S3_SD{slash}SPI3_MOSI{slash}T3C2{slash}SPI1_MOSI-Pad41)") (class "Default")
      (node (ref "U10") (pin "41") (pinfunction "PB5/I2C1_SMBA/I2S3_SD/SPI3_MOSI/T3C2/SPI1_MOSI_41") (pintype "passive"))
    )
    (net (code "70") (name "unconnected-(U10-PC13-TAMPER-RTC-Pad2)") (class "Default")
      (node (ref "U10") (pin "2") (pinfunction "PC13-TAMPER-RTC_2") (pintype "passive"))
    )
    (net (code "71") (name "unconnected-(U10-PC14-OSC32_IN-Pad3)") (class "Default")
      (node (ref "U10") (pin "3") (pinfunction "PC14-OSC32_IN_3") (pintype "passive"))
    )
    (net (code "72") (name "unconnected-(U10-PC15-OSC32_OUT-Pad4)") (class "Default")
      (node (ref "U10") (pin "4") (pinfunction "PC15-OSC32_OUT_4") (pintype "passive"))
    )
    (net (code "73") (name "unconnected-(U12-Vref-Pad5)") (class "Default")
      (node (ref "U12") (pin "5") (pinfunction "Vref_5") (pintype "passive+no_connect"))
    )
  )
)
